# PCI.net
KiCad netlist of a schematic drawn in Altium Designer
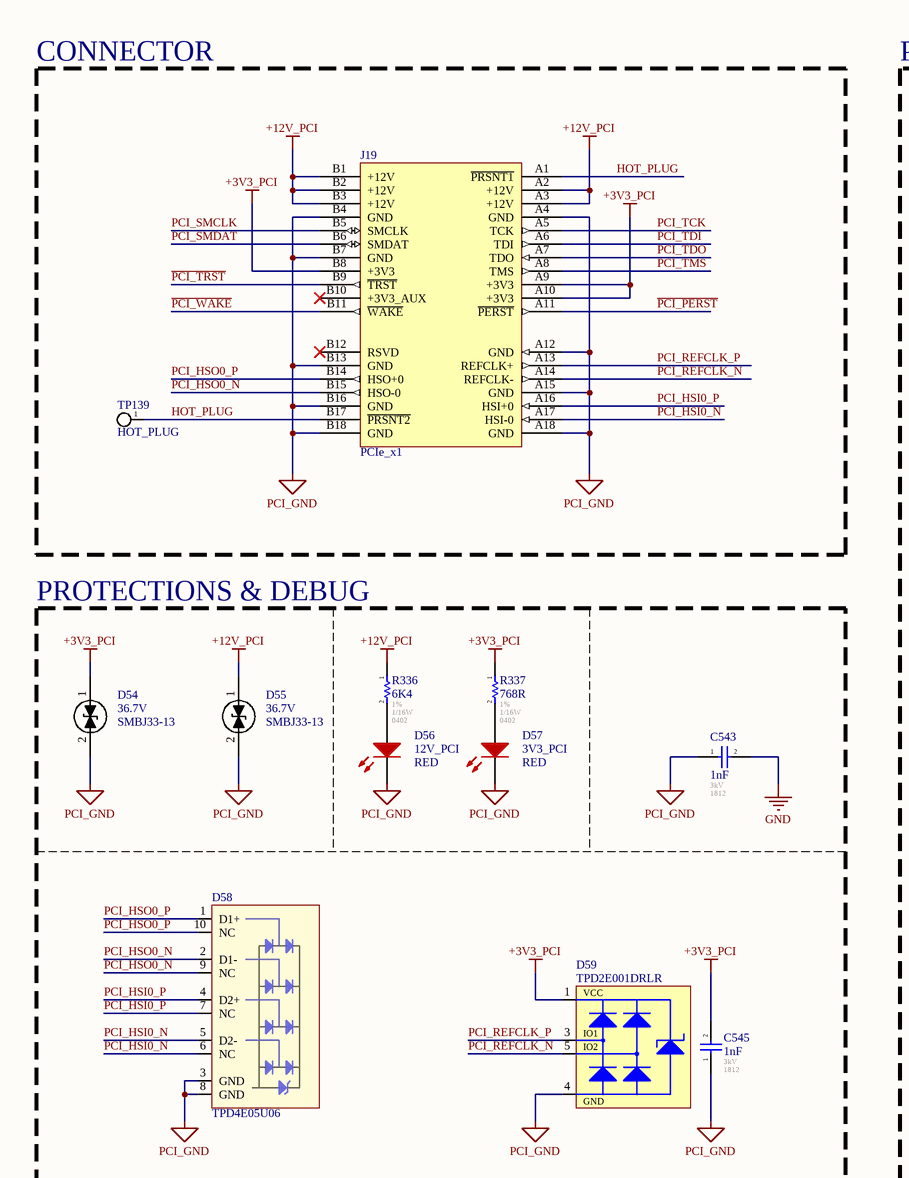
[diagram p0: PCI.SchDoc, top left]
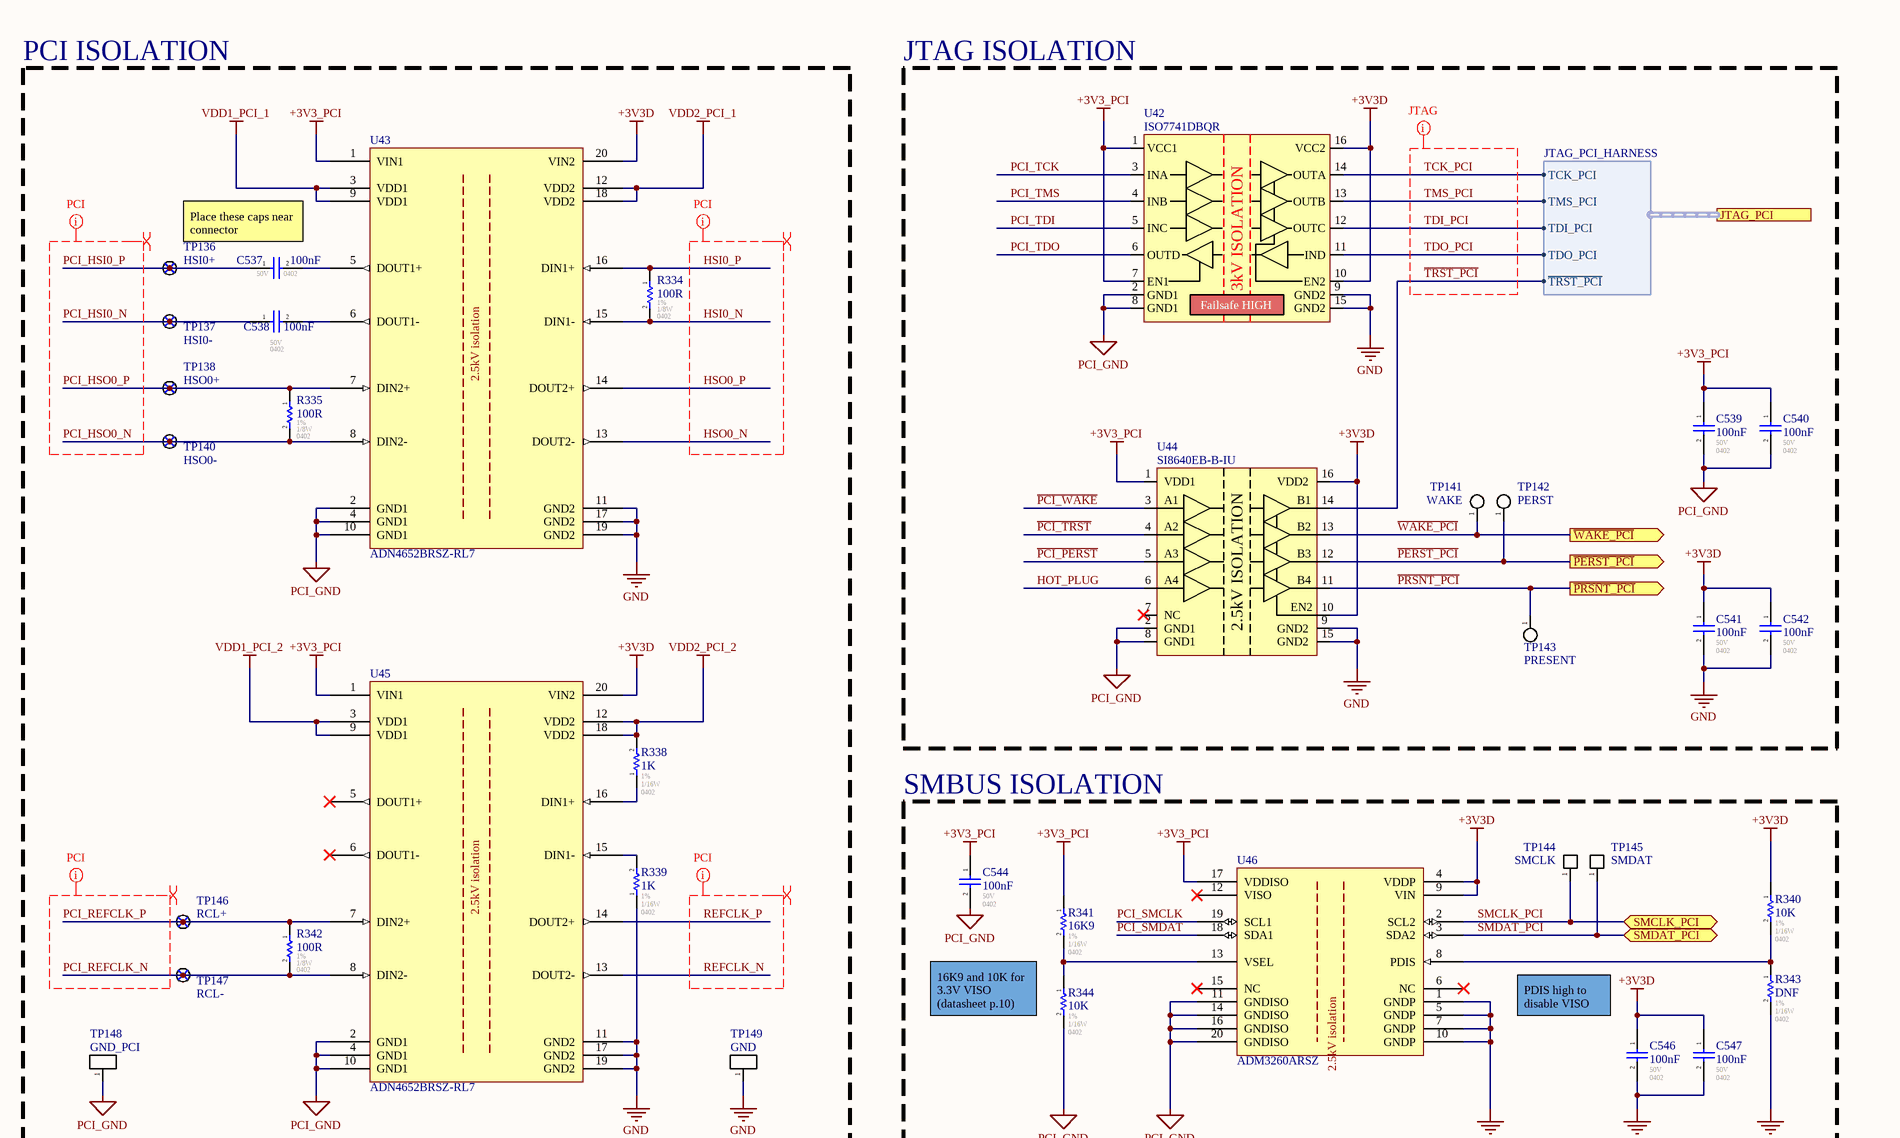
[diagram p1: PCI.SchDoc, top right]
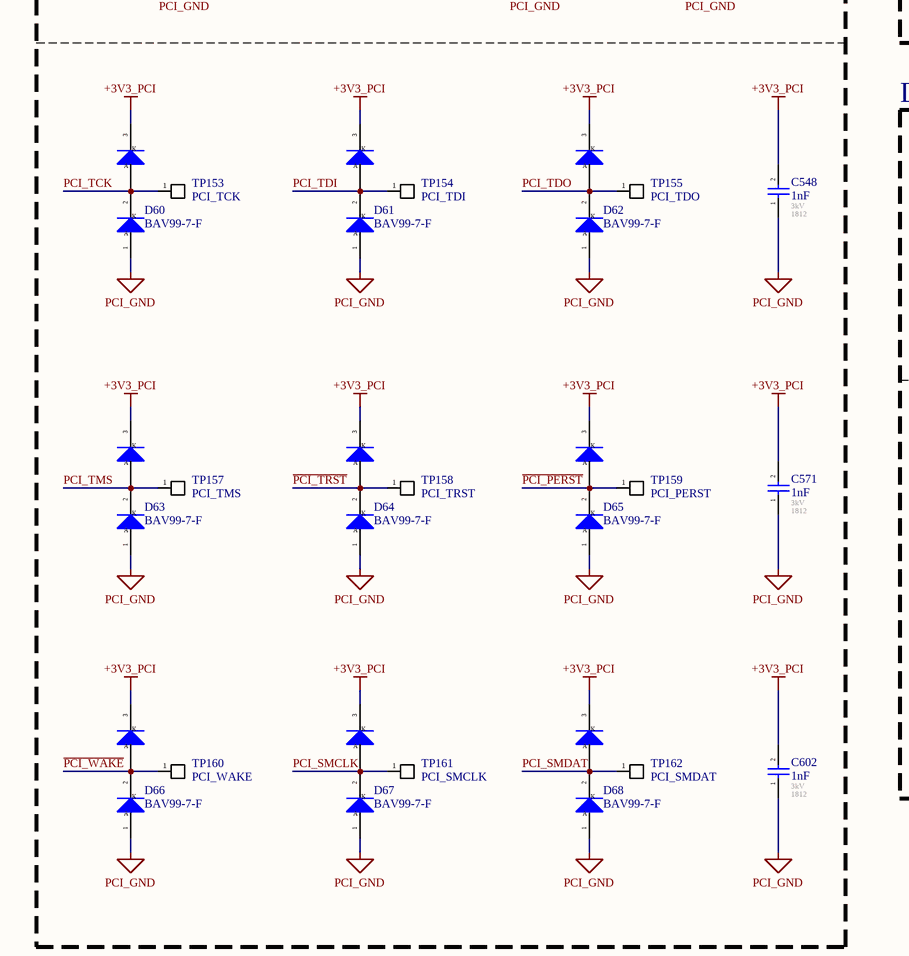
[diagram p2: PCI.SchDoc, bottom left]
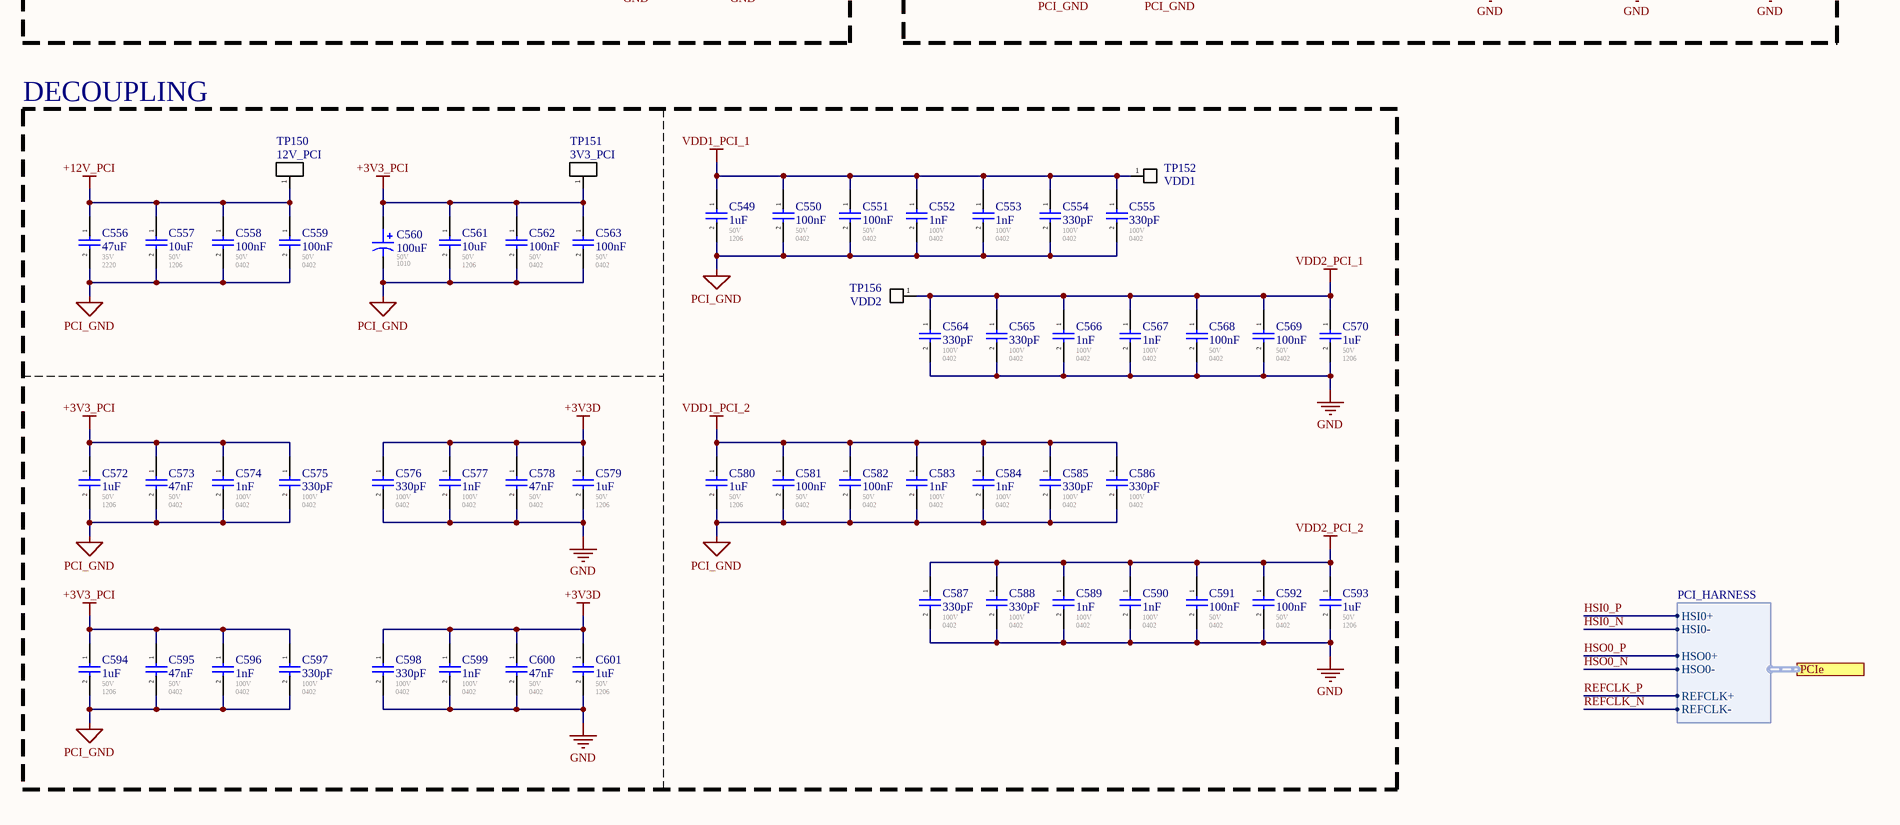
[diagram p3: PCI.SchDoc, bottom right]

(export (version "E")
  (design (tool "Eeschema 10.0.6"))
  (components
    (comp (ref "C537")
      (value "100nF")
      (footprint "0402")
      (description "GCM155R71H104KE02J\r\n0402 100nF 10% X7R Ceramic Capacitor")
      (fields
        (field (name "MFR") "Murata")
        (field (name "PART#") "GCM155R71H104KE02J")
        (field (name "VOLTAGE - RATED") "50V")
      )
      (libsource (lib "Symbols") (part "CAP_CER"))
    )
    (comp (ref "C538")
      (value "100nF")
      (footprint "0402")
      (description "GCM155R71H104KE02J\r\n0402 100nF 10% X7R Ceramic Capacitor")
      (fields
        (field (name "MFR") "Murata")
        (field (name "PART#") "GCM155R71H104KE02J")
        (field (name "VOLTAGE - RATED") "50V")
      )
      (libsource (lib "Symbols") (part "CAP_CER"))
    )
    (comp (ref "C539")
      (value "100nF")
      (footprint "0402")
      (description "GCM155R71H104KE02J\r\n0402 100nF 10% X7R Ceramic Capacitor")
      (fields
        (field (name "MFR") "Murata")
        (field (name "PART#") "GCM155R71H104KE02J")
        (field (name "VOLTAGE - RATED") "50V")
      )
      (libsource (lib "Symbols") (part "CAP_CER"))
    )
    (comp (ref "C540")
      (value "100nF")
      (footprint "0402")
      (description "GCM155R71H104KE02J\r\n0402 100nF 10% X7R Ceramic Capacitor")
      (fields
        (field (name "MFR") "Murata")
        (field (name "PART#") "GCM155R71H104KE02J")
        (field (name "VOLTAGE - RATED") "50V")
      )
      (libsource (lib "Symbols") (part "CAP_CER"))
    )
    (comp (ref "C541")
      (value "100nF")
      (footprint "0402")
      (description "GCM155R71H104KE02J\r\n0402 100nF 10% X7R Ceramic Capacitor")
      (fields
        (field (name "MFR") "Murata")
        (field (name "PART#") "GCM155R71H104KE02J")
        (field (name "VOLTAGE - RATED") "50V")
      )
      (libsource (lib "Symbols") (part "CAP_CER"))
    )
    (comp (ref "C542")
      (value "100nF")
      (footprint "0402")
      (description "GCM155R71H104KE02J\r\n0402 100nF 10% X7R Ceramic Capacitor")
      (fields
        (field (name "MFR") "Murata")
        (field (name "PART#") "GCM155R71H104KE02J")
        (field (name "VOLTAGE - RATED") "50V")
      )
      (libsource (lib "Symbols") (part "CAP_CER"))
    )
    (comp (ref "C543")
      (value "1nF")
      (footprint "1812")
      (description "C1812C102KHRACAUTO\r\n0402 470pF 10% X7R Ceramic Capacitor")
      (fields
        (field (name "MFR") "KEMET")
        (field (name "PART#") "C1812C102KHRACAUTO")
        (field (name "VOLTAGE - RATED") "3kV")
      )
      (libsource (lib "Symbols") (part "CAP_CER"))
    )
    (comp (ref "C544")
      (value "100nF")
      (footprint "0402")
      (description "GCM155R71H104KE02J\r\n0402 100nF 10% X7R Ceramic Capacitor")
      (fields
        (field (name "MFR") "Murata")
        (field (name "PART#") "GCM155R71H104KE02J")
        (field (name "VOLTAGE - RATED") "50V")
      )
      (libsource (lib "Symbols") (part "CAP_CER"))
    )
    (comp (ref "C545")
      (value "1nF")
      (footprint "1812")
      (description "C1812C102KHRACAUTO\r\n0402 470pF 10% X7R Ceramic Capacitor")
      (fields
        (field (name "MFR") "KEMET")
        (field (name "PART#") "C1812C102KHRACAUTO")
        (field (name "VOLTAGE - RATED") "3kV")
      )
      (libsource (lib "Symbols") (part "CAP_CER"))
    )
    (comp (ref "C546")
      (value "100nF")
      (footprint "0402")
      (description "GCM155R71H104KE02J\r\n0402 100nF 10% X7R Ceramic Capacitor")
      (fields
        (field (name "MFR") "Murata")
        (field (name "PART#") "GCM155R71H104KE02J")
        (field (name "VOLTAGE - RATED") "50V")
      )
      (libsource (lib "Symbols") (part "CAP_CER"))
    )
    (comp (ref "C547")
      (value "100nF")
      (footprint "0402")
      (description "GCM155R71H104KE02J\r\n0402 100nF 10% X7R Ceramic Capacitor")
      (fields
        (field (name "MFR") "Murata")
        (field (name "PART#") "GCM155R71H104KE02J")
        (field (name "VOLTAGE - RATED") "50V")
      )
      (libsource (lib "Symbols") (part "CAP_CER"))
    )
    (comp (ref "C548")
      (value "1nF")
      (footprint "1812")
      (description "C1812C102KHRACAUTO\r\n0402 470pF 10% X7R Ceramic Capacitor")
      (fields
        (field (name "MFR") "KEMET")
        (field (name "PART#") "C1812C102KHRACAUTO")
        (field (name "VOLTAGE - RATED") "3kV")
      )
      (libsource (lib "Symbols") (part "CAP_CER"))
    )
    (comp (ref "C549")
      (value "1uF")
      (footprint "1206")
      (description "GCJ31CR71H105KA12L\r\n1206 1uF 10% X7R Ceramic Capacitor")
      (fields
        (field (name "MFR") "Murata")
        (field (name "PART#") "GCJ31CR71H105KA12L")
        (field (name "VOLTAGE - RATED") "50V")
      )
      (libsource (lib "Symbols") (part "CAP_CER"))
    )
    (comp (ref "C550")
      (value "100nF")
      (footprint "0402")
      (description "GCM155R71H104KE02J\r\n0402 100nF 10% X7R Ceramic Capacitor")
      (fields
        (field (name "MFR") "Murata")
        (field (name "PART#") "GCM155R71H104KE02J")
        (field (name "VOLTAGE - RATED") "50V")
      )
      (libsource (lib "Symbols") (part "CAP_CER"))
    )
    (comp (ref "C551")
      (value "100nF")
      (footprint "0402")
      (description "GCM155R71H104KE02J\r\n0402 100nF 10% X7R Ceramic Capacitor")
      (fields
        (field (name "MFR") "Murata")
        (field (name "PART#") "GCM155R71H104KE02J")
        (field (name "VOLTAGE - RATED") "50V")
      )
      (libsource (lib "Symbols") (part "CAP_CER"))
    )
    (comp (ref "C552")
      (value "1nF")
      (footprint "0402")
      (description "GCM155R72A102KA37D\r\n0402 1nF 10% X7R Ceramic Capacitor")
      (fields
        (field (name "MFR") "Murata")
        (field (name "PART#") "GCM155R72A102KA37D")
        (field (name "VOLTAGE - RATED") "100V")
      )
      (libsource (lib "Symbols") (part "CAP_CER"))
    )
    (comp (ref "C553")
      (value "1nF")
      (footprint "0402")
      (description "GCM155R72A102KA37D\r\n0402 1nF 10% X7R Ceramic Capacitor")
      (fields
        (field (name "MFR") "Murata")
        (field (name "PART#") "GCM155R72A102KA37D")
        (field (name "VOLTAGE - RATED") "100V")
      )
      (libsource (lib "Symbols") (part "CAP_CER"))
    )
    (comp (ref "C554")
      (value "330pF")
      (footprint "0402")
      (description "GCM155R72A331KA37D\r\n0402 330pF 10% X7R Ceramic Capacitor")
      (fields
        (field (name "MFR") "Murata")
        (field (name "PART#") "GCM155R72A331KA37D")
        (field (name "VOLTAGE - RATED") "100V")
      )
      (libsource (lib "Symbols") (part "CAP_CER"))
    )
    (comp (ref "C555")
      (value "330pF")
      (footprint "0402")
      (description "GCM155R72A331KA37D\r\n0402 330pF 10% X7R Ceramic Capacitor")
      (fields
        (field (name "MFR") "Murata")
        (field (name "PART#") "GCM155R72A331KA37D")
        (field (name "VOLTAGE - RATED") "100V")
      )
      (libsource (lib "Symbols") (part "CAP_CER"))
    )
    (comp (ref "C556")
      (value "47uF")
      (footprint "2220")
      (description "CGA9N1X7R1V476M230KC\r\n2220 47uF 20% X7R Ceramic Capacitor")
      (fields
        (field (name "MFR") "TDK")
        (field (name "VOLTAGE - RATED") "35V")
        (field (name "TOLERANCE") "20%")
      )
      (libsource (lib "Symbols") (part "CAP_CER"))
    )
    (comp (ref "C557")
      (value "10uF")
      (footprint "1206")
      (description "GRT31CR61H106KE01L\r\n1206 10uF 10% X5R Ceramic Capacitor")
      (fields
        (field (name "MFR") "Murata")
        (field (name "VOLTAGE - RATED") "50V")
        (field (name "TOLERANCE") "10%")
      )
      (libsource (lib "Symbols") (part "CAP_CER"))
    )
    (comp (ref "C558")
      (value "100nF")
      (footprint "0402")
      (description "GCM155R71H104KE02J\r\n0402 100nF 10% X7R Ceramic Capacitor")
      (fields
        (field (name "MFR") "Murata")
        (field (name "PART#") "GCM155R71H104KE02J")
        (field (name "VOLTAGE - RATED") "50V")
      )
      (libsource (lib "Symbols") (part "CAP_CER"))
    )
    (comp (ref "C559")
      (value "100nF")
      (footprint "0402")
      (description "GCM155R71H104KE02J\r\n0402 100nF 10% X7R Ceramic Capacitor")
      (fields
        (field (name "MFR") "Murata")
        (field (name "PART#") "GCM155R71H104KE02J")
        (field (name "VOLTAGE - RATED") "50V")
      )
      (libsource (lib "Symbols") (part "CAP_CER"))
    )
    (comp (ref "C560")
      (value "100uF")
      (footprint "CAP_ALU_1010_vishay")
      (description "CAP - ALU 100uF 20% 50V - 1010")
      (fields
        (field (name "MFG") "Vishay Dale")
        (field (name "MFG PART NUMBER") "MAL215099101E3")
        (field (name "VOLTAGE") "50V")
        (field (name "PACKAGE") "1010")
        (field (name "CREATEDBY") "Jonathan Bouchard")
      )
      (libsource (lib "S7CAS_LIB2023") (part "CAP_ALU_MAL215099101E3"))
    )
    (comp (ref "C561")
      (value "10uF")
      (footprint "1206")
      (description "GRT31CR61H106KE01L\r\n1206 10uF 10% X5R Ceramic Capacitor")
      (fields
        (field (name "MFR") "Murata")
        (field (name "VOLTAGE - RATED") "50V")
        (field (name "TOLERANCE") "10%")
      )
      (libsource (lib "Symbols") (part "CAP_CER"))
    )
    (comp (ref "C562")
      (value "100nF")
      (footprint "0402")
      (description "GCM155R71H104KE02J\r\n0402 100nF 10% X7R Ceramic Capacitor")
      (fields
        (field (name "MFR") "Murata")
        (field (name "PART#") "GCM155R71H104KE02J")
        (field (name "VOLTAGE - RATED") "50V")
      )
      (libsource (lib "Symbols") (part "CAP_CER"))
    )
    (comp (ref "C563")
      (value "100nF")
      (footprint "0402")
      (description "GCM155R71H104KE02J\r\n0402 100nF 10% X7R Ceramic Capacitor")
      (fields
        (field (name "MFR") "Murata")
        (field (name "PART#") "GCM155R71H104KE02J")
        (field (name "VOLTAGE - RATED") "50V")
      )
      (libsource (lib "Symbols") (part "CAP_CER"))
    )
    (comp (ref "C564")
      (value "330pF")
      (footprint "0402")
      (description "GCM155R72A331KA37D\r\n0402 330pF 10% X7R Ceramic Capacitor")
      (fields
        (field (name "MFR") "Murata")
        (field (name "PART#") "GCM155R72A331KA37D")
        (field (name "VOLTAGE - RATED") "100V")
      )
      (libsource (lib "Symbols") (part "CAP_CER"))
    )
    (comp (ref "C565")
      (value "330pF")
      (footprint "0402")
      (description "GCM155R72A331KA37D\r\n0402 330pF 10% X7R Ceramic Capacitor")
      (fields
        (field (name "MFR") "Murata")
        (field (name "PART#") "GCM155R72A331KA37D")
        (field (name "VOLTAGE - RATED") "100V")
      )
      (libsource (lib "Symbols") (part "CAP_CER"))
    )
    (comp (ref "C566")
      (value "1nF")
      (footprint "0402")
      (description "GCM155R72A102KA37D\r\n0402 1nF 10% X7R Ceramic Capacitor")
      (fields
        (field (name "MFR") "Murata")
        (field (name "PART#") "GCM155R72A102KA37D")
        (field (name "VOLTAGE - RATED") "100V")
      )
      (libsource (lib "Symbols") (part "CAP_CER"))
    )
    (comp (ref "C567")
      (value "1nF")
      (footprint "0402")
      (description "GCM155R72A102KA37D\r\n0402 1nF 10% X7R Ceramic Capacitor")
      (fields
        (field (name "MFR") "Murata")
        (field (name "PART#") "GCM155R72A102KA37D")
        (field (name "VOLTAGE - RATED") "100V")
      )
      (libsource (lib "Symbols") (part "CAP_CER"))
    )
    (comp (ref "C568")
      (value "100nF")
      (footprint "0402")
      (description "GCM155R71H104KE02J\r\n0402 100nF 10% X7R Ceramic Capacitor")
      (fields
        (field (name "MFR") "Murata")
        (field (name "PART#") "GCM155R71H104KE02J")
        (field (name "VOLTAGE - RATED") "50V")
      )
      (libsource (lib "Symbols") (part "CAP_CER"))
    )
    (comp (ref "C569")
      (value "100nF")
      (footprint "0402")
      (description "GCM155R71H104KE02J\r\n0402 100nF 10% X7R Ceramic Capacitor")
      (fields
        (field (name "MFR") "Murata")
        (field (name "PART#") "GCM155R71H104KE02J")
        (field (name "VOLTAGE - RATED") "50V")
      )
      (libsource (lib "Symbols") (part "CAP_CER"))
    )
    (comp (ref "C570")
      (value "1uF")
      (footprint "1206")
      (description "GCJ31CR71H105KA12L\r\n1206 1uF 10% X7R Ceramic Capacitor")
      (fields
        (field (name "MFR") "Murata")
        (field (name "PART#") "GCJ31CR71H105KA12L")
        (field (name "VOLTAGE - RATED") "50V")
      )
      (libsource (lib "Symbols") (part "CAP_CER"))
    )
    (comp (ref "C571")
      (value "1nF")
      (footprint "1812")
      (description "C1812C102KHRACAUTO\r\n0402 470pF 10% X7R Ceramic Capacitor")
      (fields
        (field (name "MFR") "KEMET")
        (field (name "PART#") "C1812C102KHRACAUTO")
        (field (name "VOLTAGE - RATED") "3kV")
      )
      (libsource (lib "Symbols") (part "CAP_CER"))
    )
    (comp (ref "C572")
      (value "1uF")
      (footprint "1206")
      (description "GCJ31CR71H105KA12L\r\n1206 1uF 10% X7R Ceramic Capacitor")
      (fields
        (field (name "MFR") "Murata")
        (field (name "PART#") "GCJ31CR71H105KA12L")
        (field (name "VOLTAGE - RATED") "50V")
      )
      (libsource (lib "Symbols") (part "CAP_CER"))
    )
    (comp (ref "C573")
      (value "47nF")
      (footprint "0402")
      (description "GCM155R71H473KE02J\r\n0402 47nF 10% X7R Ceramic Capacitor")
      (fields
        (field (name "MFR") "Murata")
        (field (name "PART#") "GCM155R71H473KE02J")
        (field (name "VOLTAGE - RATED") "50V")
      )
      (libsource (lib "Symbols") (part "CAP_CER"))
    )
    (comp (ref "C574")
      (value "1nF")
      (footprint "0402")
      (description "GCM155R72A102KA37D\r\n0402 1nF 10% X7R Ceramic Capacitor")
      (fields
        (field (name "MFR") "Murata")
        (field (name "PART#") "GCM155R72A102KA37D")
        (field (name "VOLTAGE - RATED") "100V")
      )
      (libsource (lib "Symbols") (part "CAP_CER"))
    )
    (comp (ref "C575")
      (value "330pF")
      (footprint "0402")
      (description "GCM155R72A331KA37D\r\n0402 330pF 10% X7R Ceramic Capacitor")
      (fields
        (field (name "MFR") "Murata")
        (field (name "PART#") "GCM155R72A331KA37D")
        (field (name "VOLTAGE - RATED") "100V")
      )
      (libsource (lib "Symbols") (part "CAP_CER"))
    )
    (comp (ref "C576")
      (value "330pF")
      (footprint "0402")
      (description "GCM155R72A331KA37D\r\n0402 330pF 10% X7R Ceramic Capacitor")
      (fields
        (field (name "MFR") "Murata")
        (field (name "PART#") "GCM155R72A331KA37D")
        (field (name "VOLTAGE - RATED") "100V")
      )
      (libsource (lib "Symbols") (part "CAP_CER"))
    )
    (comp (ref "C577")
      (value "1nF")
      (footprint "0402")
      (description "GCM155R72A102KA37D\r\n0402 1nF 10% X7R Ceramic Capacitor")
      (fields
        (field (name "MFR") "Murata")
        (field (name "PART#") "GCM155R72A102KA37D")
        (field (name "VOLTAGE - RATED") "100V")
      )
      (libsource (lib "Symbols") (part "CAP_CER"))
    )
    (comp (ref "C578")
      (value "47nF")
      (footprint "0402")
      (description "GCM155R71H473KE02J\r\n0402 47nF 10% X7R Ceramic Capacitor")
      (fields
        (field (name "MFR") "Murata")
        (field (name "PART#") "GCM155R71H473KE02J")
        (field (name "VOLTAGE - RATED") "50V")
      )
      (libsource (lib "Symbols") (part "CAP_CER"))
    )
    (comp (ref "C579")
      (value "1uF")
      (footprint "1206")
      (description "GCJ31CR71H105KA12L\r\n1206 1uF 10% X7R Ceramic Capacitor")
      (fields
        (field (name "MFR") "Murata")
        (field (name "PART#") "GCJ31CR71H105KA12L")
        (field (name "VOLTAGE - RATED") "50V")
      )
      (libsource (lib "Symbols") (part "CAP_CER"))
    )
    (comp (ref "C580")
      (value "1uF")
      (footprint "1206")
      (description "GCJ31CR71H105KA12L\r\n1206 1uF 10% X7R Ceramic Capacitor")
      (fields
        (field (name "MFR") "Murata")
        (field (name "PART#") "GCJ31CR71H105KA12L")
        (field (name "VOLTAGE - RATED") "50V")
      )
      (libsource (lib "Symbols") (part "CAP_CER"))
    )
    (comp (ref "C581")
      (value "100nF")
      (footprint "0402")
      (description "GCM155R71H104KE02J\r\n0402 100nF 10% X7R Ceramic Capacitor")
      (fields
        (field (name "MFR") "Murata")
        (field (name "PART#") "GCM155R71H104KE02J")
        (field (name "VOLTAGE - RATED") "50V")
      )
      (libsource (lib "Symbols") (part "CAP_CER"))
    )
    (comp (ref "C582")
      (value "100nF")
      (footprint "0402")
      (description "GCM155R71H104KE02J\r\n0402 100nF 10% X7R Ceramic Capacitor")
      (fields
        (field (name "MFR") "Murata")
        (field (name "PART#") "GCM155R71H104KE02J")
        (field (name "VOLTAGE - RATED") "50V")
      )
      (libsource (lib "Symbols") (part "CAP_CER"))
    )
    (comp (ref "C583")
      (value "1nF")
      (footprint "0402")
      (description "GCM155R72A102KA37D\r\n0402 1nF 10% X7R Ceramic Capacitor")
      (fields
        (field (name "MFR") "Murata")
        (field (name "PART#") "GCM155R72A102KA37D")
        (field (name "VOLTAGE - RATED") "100V")
      )
      (libsource (lib "Symbols") (part "CAP_CER"))
    )
    (comp (ref "C584")
      (value "1nF")
      (footprint "0402")
      (description "GCM155R72A102KA37D\r\n0402 1nF 10% X7R Ceramic Capacitor")
      (fields
        (field (name "MFR") "Murata")
        (field (name "PART#") "GCM155R72A102KA37D")
        (field (name "VOLTAGE - RATED") "100V")
      )
      (libsource (lib "Symbols") (part "CAP_CER"))
    )
    (comp (ref "C585")
      (value "330pF")
      (footprint "0402")
      (description "GCM155R72A331KA37D\r\n0402 330pF 10% X7R Ceramic Capacitor")
      (fields
        (field (name "MFR") "Murata")
        (field (name "PART#") "GCM155R72A331KA37D")
        (field (name "VOLTAGE - RATED") "100V")
      )
      (libsource (lib "Symbols") (part "CAP_CER"))
    )
    (comp (ref "C586")
      (value "330pF")
      (footprint "0402")
      (description "GCM155R72A331KA37D\r\n0402 330pF 10% X7R Ceramic Capacitor")
      (fields
        (field (name "MFR") "Murata")
        (field (name "PART#") "GCM155R72A331KA37D")
        (field (name "VOLTAGE - RATED") "100V")
      )
      (libsource (lib "Symbols") (part "CAP_CER"))
    )
    (comp (ref "C587")
      (value "330pF")
      (footprint "0402")
      (description "GCM155R72A331KA37D\r\n0402 330pF 10% X7R Ceramic Capacitor")
      (fields
        (field (name "MFR") "Murata")
        (field (name "PART#") "GCM155R72A331KA37D")
        (field (name "VOLTAGE - RATED") "100V")
      )
      (libsource (lib "Symbols") (part "CAP_CER"))
    )
    (comp (ref "C588")
      (value "330pF")
      (footprint "0402")
      (description "GCM155R72A331KA37D\r\n0402 330pF 10% X7R Ceramic Capacitor")
      (fields
        (field (name "MFR") "Murata")
        (field (name "PART#") "GCM155R72A331KA37D")
        (field (name "VOLTAGE - RATED") "100V")
      )
      (libsource (lib "Symbols") (part "CAP_CER"))
    )
    (comp (ref "C589")
      (value "1nF")
      (footprint "0402")
      (description "GCM155R72A102KA37D\r\n0402 1nF 10% X7R Ceramic Capacitor")
      (fields
        (field (name "MFR") "Murata")
        (field (name "PART#") "GCM155R72A102KA37D")
        (field (name "VOLTAGE - RATED") "100V")
      )
      (libsource (lib "Symbols") (part "CAP_CER"))
    )
    (comp (ref "C590")
      (value "1nF")
      (footprint "0402")
      (description "GCM155R72A102KA37D\r\n0402 1nF 10% X7R Ceramic Capacitor")
      (fields
        (field (name "MFR") "Murata")
        (field (name "PART#") "GCM155R72A102KA37D")
        (field (name "VOLTAGE - RATED") "100V")
      )
      (libsource (lib "Symbols") (part "CAP_CER"))
    )
    (comp (ref "C591")
      (value "100nF")
      (footprint "0402")
      (description "GCM155R71H104KE02J\r\n0402 100nF 10% X7R Ceramic Capacitor")
      (fields
        (field (name "MFR") "Murata")
        (field (name "PART#") "GCM155R71H104KE02J")
        (field (name "VOLTAGE - RATED") "50V")
      )
      (libsource (lib "Symbols") (part "CAP_CER"))
    )
    (comp (ref "C592")
      (value "100nF")
      (footprint "0402")
      (description "GCM155R71H104KE02J\r\n0402 100nF 10% X7R Ceramic Capacitor")
      (fields
        (field (name "MFR") "Murata")
        (field (name "PART#") "GCM155R71H104KE02J")
        (field (name "VOLTAGE - RATED") "50V")
      )
      (libsource (lib "Symbols") (part "CAP_CER"))
    )
    (comp (ref "C593")
      (value "1uF")
      (footprint "1206")
      (description "GCJ31CR71H105KA12L\r\n1206 1uF 10% X7R Ceramic Capacitor")
      (fields
        (field (name "MFR") "Murata")
        (field (name "PART#") "GCJ31CR71H105KA12L")
        (field (name "VOLTAGE - RATED") "50V")
      )
      (libsource (lib "Symbols") (part "CAP_CER"))
    )
    (comp (ref "C594")
      (value "1uF")
      (footprint "1206")
      (description "GCJ31CR71H105KA12L\r\n1206 1uF 10% X7R Ceramic Capacitor")
      (fields
        (field (name "MFR") "Murata")
        (field (name "PART#") "GCJ31CR71H105KA12L")
        (field (name "VOLTAGE - RATED") "50V")
      )
      (libsource (lib "Symbols") (part "CAP_CER"))
    )
    (comp (ref "C595")
      (value "47nF")
      (footprint "0402")
      (description "GCM155R71H473KE02J\r\n0402 47nF 10% X7R Ceramic Capacitor")
      (fields
        (field (name "MFR") "Murata")
        (field (name "PART#") "GCM155R71H473KE02J")
        (field (name "VOLTAGE - RATED") "50V")
      )
      (libsource (lib "Symbols") (part "CAP_CER"))
    )
    (comp (ref "C596")
      (value "1nF")
      (footprint "0402")
      (description "GCM155R72A102KA37D\r\n0402 1nF 10% X7R Ceramic Capacitor")
      (fields
        (field (name "MFR") "Murata")
        (field (name "PART#") "GCM155R72A102KA37D")
        (field (name "VOLTAGE - RATED") "100V")
      )
      (libsource (lib "Symbols") (part "CAP_CER"))
    )
    (comp (ref "C597")
      (value "330pF")
      (footprint "0402")
      (description "GCM155R72A331KA37D\r\n0402 330pF 10% X7R Ceramic Capacitor")
      (fields
        (field (name "MFR") "Murata")
        (field (name "PART#") "GCM155R72A331KA37D")
        (field (name "VOLTAGE - RATED") "100V")
      )
      (libsource (lib "Symbols") (part "CAP_CER"))
    )
    (comp (ref "C598")
      (value "330pF")
      (footprint "0402")
      (description "GCM155R72A331KA37D\r\n0402 330pF 10% X7R Ceramic Capacitor")
      (fields
        (field (name "MFR") "Murata")
        (field (name "PART#") "GCM155R72A331KA37D")
        (field (name "VOLTAGE - RATED") "100V")
      )
      (libsource (lib "Symbols") (part "CAP_CER"))
    )
    (comp (ref "C599")
      (value "1nF")
      (footprint "0402")
      (description "GCM155R72A102KA37D\r\n0402 1nF 10% X7R Ceramic Capacitor")
      (fields
        (field (name "MFR") "Murata")
        (field (name "PART#") "GCM155R72A102KA37D")
        (field (name "VOLTAGE - RATED") "100V")
      )
      (libsource (lib "Symbols") (part "CAP_CER"))
    )
    (comp (ref "C600")
      (value "47nF")
      (footprint "0402")
      (description "GCM155R71H473KE02J\r\n0402 47nF 10% X7R Ceramic Capacitor")
      (fields
        (field (name "MFR") "Murata")
        (field (name "PART#") "GCM155R71H473KE02J")
        (field (name "VOLTAGE - RATED") "50V")
      )
      (libsource (lib "Symbols") (part "CAP_CER"))
    )
    (comp (ref "C601")
      (value "1uF")
      (footprint "1206")
      (description "GCJ31CR71H105KA12L\r\n1206 1uF 10% X7R Ceramic Capacitor")
      (fields
        (field (name "MFR") "Murata")
        (field (name "PART#") "GCJ31CR71H105KA12L")
        (field (name "VOLTAGE - RATED") "50V")
      )
      (libsource (lib "Symbols") (part "CAP_CER"))
    )
    (comp (ref "C602")
      (value "1nF")
      (footprint "1812")
      (description "C1812C102KHRACAUTO\r\n0402 470pF 10% X7R Ceramic Capacitor")
      (fields
        (field (name "MFR") "KEMET")
        (field (name "PART#") "C1812C102KHRACAUTO")
        (field (name "VOLTAGE - RATED") "3kV")
      )
      (libsource (lib "Symbols") (part "CAP_CER"))
    )
    (comp (ref "D54")
      (value "SMBJ33-13")
      (footprint "DO214AA (SMB)")
      (description "53.3V Clamp 11.3A Ipp Tvs Diode Surface Mount SMB")
      (fields (field (name "MFR") "SMBJ33CAQ-13-F") (field (name "VOLTAGE - BREAKDOWN") "36.7V"))
      (libsource (lib "Symbols") (part "DIODE_TVS"))
    )
    (comp (ref "D55")
      (value "SMBJ33-13")
      (footprint "DO214AA (SMB)")
      (description "53.3V Clamp 11.3A Ipp Tvs Diode Surface Mount SMB")
      (fields (field (name "MFR") "SMBJ33CAQ-13-F") (field (name "VOLTAGE - BREAKDOWN") "36.7V"))
      (libsource (lib "Symbols") (part "DIODE_TVS"))
    )
    (comp (ref "D56")
      (value "12V_PCI")
      (footprint "LED_0603")
      (description "LED - 620nM RED 2mA - 0603")
      (fields
        (field (name "VOLTAGE") "1.8V")
        (field (name "MFG") "ROHM Semiconductor")
        (field (name "ALTIUM_VALUE") "RED")
        (field (name "CREATEDBY") "Jonathan Bouchard")
      )
      (libsource (lib "S7CAS_LIB2023") (part "LED_SML-311UTT86"))
    )
    (comp (ref "D57")
      (value "3V3_PCI")
      (footprint "LED_0603")
      (description "LED - 620nM RED 2mA - 0603")
      (fields
        (field (name "VOLTAGE") "1.8V")
        (field (name "MFG") "ROHM Semiconductor")
        (field (name "ALTIUM_VALUE") "RED")
        (field (name "CREATEDBY") "Jonathan Bouchard")
      )
      (libsource (lib "S7CAS_LIB2023") (part "LED_SML-311UTT86"))
    )
    (comp (ref "D58")
      (value "TPD4E05U06")
      (footprint "TVS_DATA_TPD4E05U06")
      (description "TVS - TVS DIODE 5.5VWM 14VC - 10SON")
      (fields
        (field (name "CREATEDBY/DATE") "Olivier Bernard / 12/3/2018")
        (field (name "VERIFIEDBY") "Caroline Paulin / 4 juillet 2018")
      )
      (libsource (lib "S7CAS_LIB2023") (part "TVS_DATA_TPD4E05U06"))
    )
    (comp (ref "D59")
      (value "TPD2E001DRLR")
      (footprint "TVS_USB_TPD2E001DRLR")
      (description "TVS - USB TVS DIODE 5.5V - SOT-553")
      (fields
        (field (name "CREATEDBY/DATE") "Jonathan Bouchard 2018-07-10")
        (field (name "VERIFIEDBY") "Arnaud Samson 16-07-18")
      )
      (libsource (lib "S7CAS_LIB2023") (part "TVS_USB_TPD2E001DRLR"))
    )
    (comp (ref "D60")
      (value "BAV99-7-F")
      (footprint "SOT23-3")
      (description "Diode Array 1 Pair Series Connection 75 V 300mA (DC) Surface Mount TO-236-3, SC-59, SOT-23-3")
      (fields (field (name "MFR") "Diodes Incorporated"))
      (libsource (lib "Symbols") (part "DIODE_TVS_DUAL"))
    )
    (comp (ref "D61")
      (value "BAV99-7-F")
      (footprint "SOT23-3")
      (description "Diode Array 1 Pair Series Connection 75 V 300mA (DC) Surface Mount TO-236-3, SC-59, SOT-23-3")
      (fields (field (name "MFR") "Diodes Incorporated"))
      (libsource (lib "Symbols") (part "DIODE_TVS_DUAL"))
    )
    (comp (ref "D62")
      (value "BAV99-7-F")
      (footprint "SOT23-3")
      (description "Diode Array 1 Pair Series Connection 75 V 300mA (DC) Surface Mount TO-236-3, SC-59, SOT-23-3")
      (fields (field (name "MFR") "Diodes Incorporated"))
      (libsource (lib "Symbols") (part "DIODE_TVS_DUAL"))
    )
    (comp (ref "D63")
      (value "BAV99-7-F")
      (footprint "SOT23-3")
      (description "Diode Array 1 Pair Series Connection 75 V 300mA (DC) Surface Mount TO-236-3, SC-59, SOT-23-3")
      (fields (field (name "MFR") "Diodes Incorporated"))
      (libsource (lib "Symbols") (part "DIODE_TVS_DUAL"))
    )
    (comp (ref "D64")
      (value "BAV99-7-F")
      (footprint "SOT23-3")
      (description "Diode Array 1 Pair Series Connection 75 V 300mA (DC) Surface Mount TO-236-3, SC-59, SOT-23-3")
      (fields (field (name "MFR") "Diodes Incorporated"))
      (libsource (lib "Symbols") (part "DIODE_TVS_DUAL"))
    )
    (comp (ref "D65")
      (value "BAV99-7-F")
      (footprint "SOT23-3")
      (description "Diode Array 1 Pair Series Connection 75 V 300mA (DC) Surface Mount TO-236-3, SC-59, SOT-23-3")
      (fields (field (name "MFR") "Diodes Incorporated"))
      (libsource (lib "Symbols") (part "DIODE_TVS_DUAL"))
    )
    (comp (ref "D66")
      (value "BAV99-7-F")
      (footprint "SOT23-3")
      (description "Diode Array 1 Pair Series Connection 75 V 300mA (DC) Surface Mount TO-236-3, SC-59, SOT-23-3")
      (fields (field (name "MFR") "Diodes Incorporated"))
      (libsource (lib "Symbols") (part "DIODE_TVS_DUAL"))
    )
    (comp (ref "D67")
      (value "BAV99-7-F")
      (footprint "SOT23-3")
      (description "Diode Array 1 Pair Series Connection 75 V 300mA (DC) Surface Mount TO-236-3, SC-59, SOT-23-3")
      (fields (field (name "MFR") "Diodes Incorporated"))
      (libsource (lib "Symbols") (part "DIODE_TVS_DUAL"))
    )
    (comp (ref "D68")
      (value "BAV99-7-F")
      (footprint "SOT23-3")
      (description "Diode Array 1 Pair Series Connection 75 V 300mA (DC) Surface Mount TO-236-3, SC-59, SOT-23-3")
      (fields (field (name "MFR") "Diodes Incorporated"))
      (libsource (lib "Symbols") (part "DIODE_TVS_DUAL"))
    )
    (comp (ref "J19") (value "PCIe_x1") (footprint "PCIe_x1") (libsource (lib "Connectors") (part "PCIe_x1")))
    (comp (ref "R334")
      (value "100R")
      (footprint "RES_0402")
      (fields
        (field (name "TOLERANCE") "1%")
        (field (name "POWER") "1/8W")
        (field (name "PACKAGE / CASE") "0402")
      )
      (libsource (lib "Symbols") (part "RESISTOR"))
    )
    (comp (ref "R335")
      (value "100R")
      (footprint "RES_0402")
      (fields
        (field (name "TOLERANCE") "1%")
        (field (name "POWER") "1/8W")
        (field (name "PACKAGE / CASE") "0402")
      )
      (libsource (lib "Symbols") (part "RESISTOR"))
    )
    (comp (ref "R336")
      (value "6K4")
      (footprint "RES_0402")
      (fields
        (field (name "TOLERANCE") "1%")
        (field (name "POWER") "1/16W")
        (field (name "PACKAGE / CASE") "0402")
      )
      (libsource (lib "Symbols") (part "RESISTOR"))
    )
    (comp (ref "R337")
      (value "768R")
      (footprint "RES_0402")
      (fields
        (field (name "TOLERANCE") "1%")
        (field (name "POWER") "1/16W")
        (field (name "PACKAGE / CASE") "0402")
      )
      (libsource (lib "Symbols") (part "RESISTOR"))
    )
    (comp (ref "R338")
      (value "1K")
      (footprint "RES_0402")
      (fields
        (field (name "TOLERANCE") "1%")
        (field (name "POWER") "1/16W")
        (field (name "PACKAGE / CASE") "0402")
      )
      (libsource (lib "Symbols") (part "RESISTOR"))
    )
    (comp (ref "R339")
      (value "1K")
      (footprint "RES_0402")
      (fields
        (field (name "TOLERANCE") "1%")
        (field (name "POWER") "1/16W")
        (field (name "PACKAGE / CASE") "0402")
      )
      (libsource (lib "Symbols") (part "RESISTOR"))
    )
    (comp (ref "R340")
      (value "10K")
      (footprint "RES_0402")
      (fields
        (field (name "TOLERANCE") "1%")
        (field (name "POWER") "1/16W")
        (field (name "PACKAGE / CASE") "0402")
      )
      (libsource (lib "Symbols") (part "RESISTOR"))
    )
    (comp (ref "R341")
      (value "16K9")
      (footprint "RES_0402")
      (fields
        (field (name "TOLERANCE") "1%")
        (field (name "POWER") "1/16W")
        (field (name "PACKAGE / CASE") "0402")
      )
      (libsource (lib "Symbols") (part "RESISTOR"))
    )
    (comp (ref "R342")
      (value "100R")
      (footprint "RES_0402")
      (fields
        (field (name "TOLERANCE") "1%")
        (field (name "POWER") "1/8W")
        (field (name "PACKAGE / CASE") "0402")
      )
      (libsource (lib "Symbols") (part "RESISTOR"))
    )
    (comp (ref "R343")
      (value "DNF")
      (footprint "RES_0402")
      (fields
        (field (name "TOLERANCE") "1%")
        (field (name "POWER") "1/16W")
        (field (name "PACKAGE / CASE") "0402")
      )
      (libsource (lib "Symbols") (part "RESISTOR"))
    )
    (comp (ref "R344")
      (value "10K")
      (footprint "RES_0402")
      (fields
        (field (name "TOLERANCE") "1%")
        (field (name "POWER") "1/16W")
        (field (name "PACKAGE / CASE") "0402")
      )
      (libsource (lib "Symbols") (part "RESISTOR"))
    )
    (comp (ref "TP136")
      (value "HSI0+")
      (footprint "TP_PAD_TINY")
      (description "Test Point")
      (libsource (lib "Symbols") (part "TESTPOINT_PAD_TINY"))
    )
    (comp (ref "TP137")
      (value "HSI0-")
      (footprint "TP_PAD_TINY")
      (description "Test Point")
      (libsource (lib "Symbols") (part "TESTPOINT_PAD_TINY"))
    )
    (comp (ref "TP138")
      (value "HSO0+")
      (footprint "TP_PAD_TINY")
      (description "Test Point")
      (libsource (lib "Symbols") (part "TESTPOINT_PAD_TINY"))
    )
    (comp (ref "TP139")
      (value "HOT_PLUG")
      (footprint "TP_PAD_SMALL")
      (description "Test Point")
      (libsource (lib "Symbols") (part "TESTPOINT_PAD_SMALL"))
    )
    (comp (ref "TP140")
      (value "HSO0-")
      (footprint "TP_PAD_TINY")
      (description "Test Point")
      (libsource (lib "Symbols") (part "TESTPOINT_PAD_TINY"))
    )
    (comp (ref "TP141")
      (value "WAKE")
      (footprint "TP_PAD_SMALL")
      (description "Test Point")
      (libsource (lib "Symbols") (part "TESTPOINT_PAD_SMALL"))
    )
    (comp (ref "TP142")
      (value "PERST")
      (footprint "TP_PAD_SMALL")
      (description "Test Point")
      (libsource (lib "Symbols") (part "TESTPOINT_PAD_SMALL"))
    )
    (comp (ref "TP143")
      (value "PRESENT")
      (footprint "TP_PAD_SMALL")
      (description "Test Point")
      (libsource (lib "Symbols") (part "TESTPOINT_PAD_SMALL"))
    )
    (comp (ref "TP144")
      (value "SMCLK")
      (footprint "TP_PAD")
      (description "Test Point")
      (libsource (lib "Symbols") (part "TESTPOINT_PAD"))
    )
    (comp (ref "TP145")
      (value "SMDAT")
      (footprint "TP_PAD")
      (description "Test Point")
      (libsource (lib "Symbols") (part "TESTPOINT_PAD"))
    )
    (comp (ref "TP146")
      (value "RCL+")
      (footprint "TP_PAD_TINY")
      (description "Test Point")
      (libsource (lib "Symbols") (part "TESTPOINT_PAD_TINY"))
    )
    (comp (ref "TP147")
      (value "RCL-")
      (footprint "TP_PAD_TINY")
      (description "Test Point")
      (libsource (lib "Symbols") (part "TESTPOINT_PAD_TINY"))
    )
    (comp (ref "TP148")
      (value "GND_PCI")
      (footprint "TP_HOLE")
      (description "Test Point")
      (libsource (lib "Symbols") (part "TESTPOINT"))
    )
    (comp (ref "TP149")
      (value "GND")
      (footprint "TP_HOLE")
      (description "Test Point")
      (libsource (lib "Symbols") (part "TESTPOINT"))
    )
    (comp (ref "TP150")
      (value "12V_PCI")
      (footprint "TP_HOLE")
      (description "Test Point")
      (libsource (lib "Symbols") (part "TESTPOINT"))
    )
    (comp (ref "TP151")
      (value "3V3_PCI")
      (footprint "TP_HOLE")
      (description "Test Point")
      (libsource (lib "Symbols") (part "TESTPOINT"))
    )
    (comp (ref "TP152")
      (value "VDD1")
      (footprint "TP_PAD")
      (description "Test Point")
      (libsource (lib "Symbols") (part "TESTPOINT_PAD"))
    )
    (comp (ref "TP153")
      (value "PCI_TCK")
      (footprint "TP_PAD")
      (description "Test Point")
      (libsource (lib "Symbols") (part "TESTPOINT_PAD"))
    )
    (comp (ref "TP154")
      (value "PCI_TDI")
      (footprint "TP_PAD")
      (description "Test Point")
      (libsource (lib "Symbols") (part "TESTPOINT_PAD"))
    )
    (comp (ref "TP155")
      (value "PCI_TDO")
      (footprint "TP_PAD")
      (description "Test Point")
      (libsource (lib "Symbols") (part "TESTPOINT_PAD"))
    )
    (comp (ref "TP156")
      (value "VDD2")
      (footprint "TP_PAD")
      (description "Test Point")
      (libsource (lib "Symbols") (part "TESTPOINT_PAD"))
    )
    (comp (ref "TP157")
      (value "PCI_TMS")
      (footprint "TP_PAD")
      (description "Test Point")
      (libsource (lib "Symbols") (part "TESTPOINT_PAD"))
    )
    (comp (ref "TP158")
      (value "PCI_TRST")
      (footprint "TP_PAD")
      (description "Test Point")
      (libsource (lib "Symbols") (part "TESTPOINT_PAD"))
    )
    (comp (ref "TP159")
      (value "PCI_PERST")
      (footprint "TP_PAD")
      (description "Test Point")
      (libsource (lib "Symbols") (part "TESTPOINT_PAD"))
    )
    (comp (ref "TP160")
      (value "PCI_WAKE")
      (footprint "TP_PAD")
      (description "Test Point")
      (libsource (lib "Symbols") (part "TESTPOINT_PAD"))
    )
    (comp (ref "TP161")
      (value "PCI_SMCLK")
      (footprint "TP_PAD")
      (description "Test Point")
      (libsource (lib "Symbols") (part "TESTPOINT_PAD"))
    )
    (comp (ref "TP162")
      (value "PCI_SMDAT")
      (footprint "TP_PAD")
      (description "Test Point")
      (libsource (lib "Symbols") (part "TESTPOINT_PAD"))
    )
    (comp (ref "U42")
      (value "ISO7741DBQR")
      (footprint "ISO_ISO7741DBQR")
      (description "ISO - Quad-Channel Digital Isolator 3/1 (Default High)- 16-SSOP")
      (fields
        (field (name "CREATEDBY/DATE") "Louis-Daniel Gaulin / 11-03-2020")
        (field (name "VERIFIEDBY") "C.Paulin - 20/04/2020")
      )
      (libsource (lib "S7CAS_LIB2023") (part "ISO_ISO7741DBQR"))
    )
    (comp (ref "U43")
      (value "ADN4652BRSZ-RL7")
      (footprint "TSSOP-20_5.3MM")
      (fields (field (name "MFR") "Analog Devices"))
      (libsource (lib "Misc") (part "ADN4652BRSZ-RL7"))
    )
    (comp (ref "U44")
      (value "SI8640EB-B-IU")
      (footprint "ISO_SI8640EB-B-IU")
      (description "ISO - Quad-Channel Digital Isolator (default HI) - 16-SSOP")
      (fields
        (field (name "CREATEDBY/DATE") "Joel Lemay 2018-06-05")
        (field (name "VERIFIEDBY") "Caroline Paulin - 12 sept 2018")
      )
      (libsource (lib "S7CAS_LIB2023") (part "ISO_SI8640EB-B-IU"))
    )
    (comp (ref "U45")
      (value "ADN4652BRSZ-RL7")
      (footprint "TSSOP-20_5.3MM")
      (fields (field (name "MFR") "Analog Devices"))
      (libsource (lib "Misc") (part "ADN4652BRSZ-RL7"))
    )
    (comp (ref "U46")
      (value "ADM3260ARSZ")
      (footprint "TSSOP-20_5.3MM")
      (description "I2C Digital Isolator 2500Vrms 2 Channel 25kV/µs CMTI 20-SSOP (0.209\", 5.30mm Width)")
      (fields (field (name "MFR") "Analog Devices"))
      (libsource (lib "Misc") (part "ADM3260ARSZ"))
    )
  )
  (nets
    (net (code "3") (name "+3V3D") (class "Default")
      (node (ref "C541") (pin "1") (pinfunction "1_1") (pintype "passive"))
      (node (ref "C542") (pin "1") (pinfunction "1_1") (pintype "passive"))
      (node (ref "C546") (pin "1") (pinfunction "1_1") (pintype "passive"))
      (node (ref "C547") (pin "1") (pinfunction "1_1") (pintype "passive"))
      (node (ref "C576") (pin "1") (pinfunction "1_1") (pintype "passive"))
      (node (ref "C577") (pin "1") (pinfunction "1_1") (pintype "passive"))
      (node (ref "C578") (pin "1") (pinfunction "1_1") (pintype "passive"))
      (node (ref "C579") (pin "1") (pinfunction "1_1") (pintype "passive"))
      (node (ref "C598") (pin "1") (pinfunction "1_1") (pintype "passive"))
      (node (ref "C599") (pin "1") (pinfunction "1_1") (pintype "passive"))
      (node (ref "C600") (pin "1") (pinfunction "1_1") (pintype "passive"))
      (node (ref "C601") (pin "1") (pinfunction "1_1") (pintype "passive"))
      (node (ref "R340") (pin "1") (pinfunction "1_1") (pintype "passive"))
      (node (ref "U42") (pin "10") (pinfunction "EN2_10") (pintype "passive"))
      (node (ref "U42") (pin "16") (pinfunction "VCC2_16") (pintype "passive"))
      (node (ref "U43") (pin "20") (pinfunction "VIN2_20") (pintype "power_in"))
      (node (ref "U44") (pin "10") (pinfunction "EN2_10") (pintype "passive"))
      (node (ref "U44") (pin "16") (pinfunction "VDD2_16") (pintype "passive"))
      (node (ref "U45") (pin "20") (pinfunction "VIN2_20") (pintype "power_in"))
      (node (ref "U46") (pin "4") (pinfunction "VDDP_4") (pintype "power_in"))
      (node (ref "U46") (pin "9") (pinfunction "VIN_9") (pintype "power_in"))
    )
    (net (code "4") (name "+3V3_PCI") (class "Default")
      (node (ref "C539") (pin "1") (pinfunction "1_1") (pintype "passive"))
      (node (ref "C540") (pin "1") (pinfunction "1_1") (pintype "passive"))
      (node (ref "C544") (pin "1") (pinfunction "1_1") (pintype "passive"))
      (node (ref "C545") (pin "2") (pinfunction "2_2") (pintype "passive"))
      (node (ref "C548") (pin "2") (pinfunction "2_2") (pintype "passive"))
      (node (ref "C560") (pin "1") (pinfunction "1_1") (pintype "passive"))
      (node (ref "C561") (pin "1") (pinfunction "1_1") (pintype "passive"))
      (node (ref "C562") (pin "1") (pinfunction "1_1") (pintype "passive"))
      (node (ref "C563") (pin "1") (pinfunction "1_1") (pintype "passive"))
      (node (ref "C571") (pin "2") (pinfunction "2_2") (pintype "passive"))
      (node (ref "C572") (pin "1") (pinfunction "1_1") (pintype "passive"))
      (node (ref "C573") (pin "1") (pinfunction "1_1") (pintype "passive"))
      (node (ref "C574") (pin "1") (pinfunction "1_1") (pintype "passive"))
      (node (ref "C575") (pin "1") (pinfunction "1_1") (pintype "passive"))
      (node (ref "C594") (pin "1") (pinfunction "1_1") (pintype "passive"))
      (node (ref "C595") (pin "1") (pinfunction "1_1") (pintype "passive"))
      (node (ref "C596") (pin "1") (pinfunction "1_1") (pintype "passive"))
      (node (ref "C597") (pin "1") (pinfunction "1_1") (pintype "passive"))
      (node (ref "C602") (pin "2") (pinfunction "2_2") (pintype "passive"))
      (node (ref "D54") (pin "1") (pinfunction "A_1") (pintype "passive"))
      (node (ref "D59") (pin "1") (pinfunction "VCC_1") (pintype "passive"))
      (node (ref "D60") (pin "3") (pinfunction "K_3") (pintype "passive"))
      (node (ref "D61") (pin "3") (pinfunction "K_3") (pintype "passive"))
      (node (ref "D62") (pin "3") (pinfunction "K_3") (pintype "passive"))
      (node (ref "D63") (pin "3") (pinfunction "K_3") (pintype "passive"))
      (node (ref "D64") (pin "3") (pinfunction "K_3") (pintype "passive"))
      (node (ref "D65") (pin "3") (pinfunction "K_3") (pintype "passive"))
      (node (ref "D66") (pin "3") (pinfunction "K_3") (pintype "passive"))
      (node (ref "D67") (pin "3") (pinfunction "K_3") (pintype "passive"))
      (node (ref "D68") (pin "3") (pinfunction "K_3") (pintype "passive"))
      (node (ref "J19") (pin "A10") (pinfunction "+3V3_A10") (pintype "power_in"))
      (node (ref "J19") (pin "A9") (pinfunction "+3V3_A9") (pintype "power_in"))
      (node (ref "J19") (pin "B8") (pinfunction "+3V3_B8") (pintype "power_in"))
      (node (ref "R337") (pin "1") (pinfunction "1_1") (pintype "passive"))
      (node (ref "R341") (pin "1") (pinfunction "1_1") (pintype "passive"))
      (node (ref "TP151") (pin "1") (pinfunction "A_1") (pintype "passive"))
      (node (ref "U42") (pin "1") (pinfunction "VCC1_1") (pintype "passive"))
      (node (ref "U42") (pin "7") (pinfunction "EN1_7") (pintype "passive"))
      (node (ref "U43") (pin "1") (pinfunction "VIN1_1") (pintype "power_in"))
      (node (ref "U44") (pin "1") (pinfunction "VDD1_1") (pintype "passive"))
      (node (ref "U45") (pin "1") (pinfunction "VIN1_1") (pintype "power_in"))
      (node (ref "U46") (pin "17") (pinfunction "VDDISO_17") (pintype "power_in"))
    )
    (net (code "5") (name "+12V_PCI") (class "Default")
      (node (ref "C556") (pin "1") (pinfunction "1_1") (pintype "passive"))
      (node (ref "C557") (pin "1") (pinfunction "1_1") (pintype "passive"))
      (node (ref "C558") (pin "1") (pinfunction "1_1") (pintype "passive"))
      (node (ref "C559") (pin "1") (pinfunction "1_1") (pintype "passive"))
      (node (ref "D55") (pin "1") (pinfunction "A_1") (pintype "passive"))
      (node (ref "J19") (pin "A2") (pinfunction "+12V_A2") (pintype "power_in"))
      (node (ref "J19") (pin "A3") (pinfunction "+12V_A3") (pintype "power_in"))
      (node (ref "J19") (pin "B1") (pinfunction "+12V_B1") (pintype "power_in"))
      (node (ref "J19") (pin "B2") (pinfunction "+12V_B2") (pintype "power_in"))
      (node (ref "J19") (pin "B3") (pinfunction "+12V_B3") (pintype "power_in"))
      (node (ref "R336") (pin "1") (pinfunction "1_1") (pintype "passive"))
      (node (ref "TP150") (pin "1") (pinfunction "A_1") (pintype "passive"))
    )
    (net (code "6") (name "/HOT_PLUG") (class "Default")
      (node (ref "J19") (pin "A1") (pinfunction "PRSNT1_A1") (pintype "passive"))
      (node (ref "J19") (pin "B17") (pinfunction "PRSNT2_B17") (pintype "passive"))
      (node (ref "TP139") (pin "1") (pinfunction "A_1") (pintype "passive"))
      (node (ref "U44") (pin "6") (pinfunction "A4_6") (pintype "passive"))
    )
    (net (code "7") (name "/HSI0_N") (class "Default")
      (node (ref "R334") (pin "2") (pinfunction "2_2") (pintype "passive"))
      (node (ref "U43") (pin "15") (pinfunction "DIN1-_15") (pintype "input"))
    )
    (net (code "8") (name "/HSI0_P") (class "Default")
      (node (ref "R334") (pin "1") (pinfunction "1_1") (pintype "passive"))
      (node (ref "U43") (pin "16") (pinfunction "DIN1+_16") (pintype "input"))
    )
    (net (code "9") (name "/HSO0_N") (class "Default")
      (node (ref "U43") (pin "13") (pinfunction "DOUT2-_13") (pintype "output"))
    )
    (net (code "10") (name "/HSO0_P") (class "Default")
      (node (ref "U43") (pin "14") (pinfunction "DOUT2+_14") (pintype "output"))
    )
    (net (code "11") (name "/PCI_HSI0_N") (class "Default")
      (node (ref "C538") (pin "1") (pinfunction "1_1") (pintype "passive"))
      (node (ref "D58") (pin "5") (pinfunction "D2-_5") (pintype "passive"))
      (node (ref "D58") (pin "6") (pinfunction "NC_6") (pintype "passive"))
      (node (ref "J19") (pin "A17") (pinfunction "HSI-0_A17") (pintype "input"))
      (node (ref "TP137") (pin "1") (pinfunction "A_1") (pintype "passive"))
    )
    (net (code "12") (name "/PCI_HSI0_P") (class "Default")
      (node (ref "C537") (pin "1") (pinfunction "1_1") (pintype "passive"))
      (node (ref "D58") (pin "4") (pinfunction "D2+_4") (pintype "passive"))
      (node (ref "D58") (pin "7") (pinfunction "NC_7") (pintype "passive"))
      (node (ref "J19") (pin "A16") (pinfunction "HSI+0_A16") (pintype "input"))
      (node (ref "TP136") (pin "1") (pinfunction "A_1") (pintype "passive"))
    )
    (net (code "13") (name "/PCI_HSO0_N") (class "Default")
      (node (ref "D58") (pin "2") (pinfunction "D1-_2") (pintype "passive"))
      (node (ref "D58") (pin "9") (pinfunction "NC_9") (pintype "passive"))
      (node (ref "J19") (pin "B15") (pinfunction "HSO-0_B15") (pintype "output"))
      (node (ref "R335") (pin "2") (pinfunction "2_2") (pintype "passive"))
      (node (ref "TP140") (pin "1") (pinfunction "A_1") (pintype "passive"))
      (node (ref "U43") (pin "8") (pinfunction "DIN2-_8") (pintype "input"))
    )
    (net (code "14") (name "/PCI_HSO0_P") (class "Default")
      (node (ref "D58") (pin "1") (pinfunction "D1+_1") (pintype "passive"))
      (node (ref "D58") (pin "10") (pinfunction "NC_10") (pintype "passive"))
      (node (ref "J19") (pin "B14") (pinfunction "HSO+0_B14") (pintype "output"))
      (node (ref "R335") (pin "1") (pinfunction "1_1") (pintype "passive"))
      (node (ref "TP138") (pin "1") (pinfunction "A_1") (pintype "passive"))
      (node (ref "U43") (pin "7") (pinfunction "DIN2+_7") (pintype "input"))
    )
    (net (code "15") (name "/PCI_PERST") (class "Default")
      (node (ref "D65") (pin "2") (pinfunction "K_2") (pintype "passive"))
      (node (ref "J19") (pin "A11") (pinfunction "PERST_A11") (pintype "output"))
      (node (ref "TP159") (pin "1") (pinfunction "A_1") (pintype "passive"))
      (node (ref "U44") (pin "5") (pinfunction "A3_5") (pintype "passive"))
    )
    (net (code "16") (name "/PCI_REFCLK_N") (class "Default")
      (node (ref "D59") (pin "5") (pinfunction "IO2_5") (pintype "passive"))
      (node (ref "J19") (pin "A14") (pinfunction "REFCLK-_A14") (pintype "output"))
      (node (ref "R342") (pin "2") (pinfunction "2_2") (pintype "passive"))
      (node (ref "TP147") (pin "1") (pinfunction "A_1") (pintype "passive"))
      (node (ref "U45") (pin "8") (pinfunction "DIN2-_8") (pintype "input"))
    )
    (net (code "17") (name "/PCI_REFCLK_P") (class "Default")
      (node (ref "D59") (pin "3") (pinfunction "IO1_3") (pintype "passive"))
      (node (ref "J19") (pin "A13") (pinfunction "REFCLK+_A13") (pintype "output"))
      (node (ref "R342") (pin "1") (pinfunction "1_1") (pintype "passive"))
      (node (ref "TP146") (pin "1") (pinfunction "A_1") (pintype "passive"))
      (node (ref "U45") (pin "7") (pinfunction "DIN2+_7") (pintype "input"))
    )
    (net (code "18") (name "/PCI_SMCLK") (class "Default")
      (node (ref "D67") (pin "2") (pinfunction "K_2") (pintype "passive"))
      (node (ref "J19") (pin "B5") (pinfunction "SMCLK_B5") (pintype "bidirectional"))
      (node (ref "TP161") (pin "1") (pinfunction "A_1") (pintype "passive"))
      (node (ref "U46") (pin "19") (pinfunction "SCL1_19") (pintype "bidirectional"))
    )
    (net (code "19") (name "/PCI_SMDAT") (class "Default")
      (node (ref "D68") (pin "2") (pinfunction "K_2") (pintype "passive"))
      (node (ref "J19") (pin "B6") (pinfunction "SMDAT_B6") (pintype "bidirectional"))
      (node (ref "TP162") (pin "1") (pinfunction "A_1") (pintype "passive"))
      (node (ref "U46") (pin "18") (pinfunction "SDA1_18") (pintype "bidirectional"))
    )
    (net (code "20") (name "/PCI_TCK") (class "Default")
      (node (ref "D60") (pin "2") (pinfunction "K_2") (pintype "passive"))
      (node (ref "J19") (pin "A5") (pinfunction "TCK_A5") (pintype "output"))
      (node (ref "TP153") (pin "1") (pinfunction "A_1") (pintype "passive"))
      (node (ref "U42") (pin "3") (pinfunction "INA_3") (pintype "passive"))
    )
    (net (code "21") (name "/PCI_TDI") (class "Default")
      (node (ref "D61") (pin "2") (pinfunction "K_2") (pintype "passive"))
      (node (ref "J19") (pin "A6") (pinfunction "TDI_A6") (pintype "output"))
      (node (ref "TP154") (pin "1") (pinfunction "A_1") (pintype "passive"))
      (node (ref "U42") (pin "5") (pinfunction "INC_5") (pintype "passive"))
    )
    (net (code "22") (name "/PCI_TDO") (class "Default")
      (node (ref "D62") (pin "2") (pinfunction "K_2") (pintype "passive"))
      (node (ref "J19") (pin "A7") (pinfunction "TDO_A7") (pintype "input"))
      (node (ref "TP155") (pin "1") (pinfunction "A_1") (pintype "passive"))
      (node (ref "U42") (pin "6") (pinfunction "OUTD_6") (pintype "passive"))
    )
    (net (code "23") (name "/PCI_TMS") (class "Default")
      (node (ref "D63") (pin "2") (pinfunction "K_2") (pintype "passive"))
      (node (ref "J19") (pin "A8") (pinfunction "TMS_A8") (pintype "output"))
      (node (ref "TP157") (pin "1") (pinfunction "A_1") (pintype "passive"))
      (node (ref "U42") (pin "4") (pinfunction "INB_4") (pintype "passive"))
    )
    (net (code "24") (name "/PCI_TRST") (class "Default")
      (node (ref "D64") (pin "2") (pinfunction "K_2") (pintype "passive"))
      (node (ref "J19") (pin "B9") (pinfunction "TRST_B9") (pintype "output"))
      (node (ref "TP158") (pin "1") (pinfunction "A_1") (pintype "passive"))
      (node (ref "U44") (pin "4") (pinfunction "A2_4") (pintype "passive"))
    )
    (net (code "25") (name "/PCI_WAKE") (class "Default")
      (node (ref "D66") (pin "2") (pinfunction "K_2") (pintype "passive"))
      (node (ref "J19") (pin "B11") (pinfunction "WAKE_B11") (pintype "output"))
      (node (ref "TP160") (pin "1") (pinfunction "A_1") (pintype "passive"))
      (node (ref "U44") (pin "3") (pinfunction "A1_3") (pintype "passive"))
    )
    (net (code "26") (name "/PERST_PCI") (class "Default")
      (node (ref "TP142") (pin "1") (pinfunction "A_1") (pintype "passive"))
      (node (ref "U44") (pin "12") (pinfunction "B3_12") (pintype "passive"))
    )
    (net (code "27") (name "/PRSNT_PCI") (class "Default")
      (node (ref "TP143") (pin "1") (pinfunction "A_1") (pintype "passive"))
      (node (ref "U44") (pin "11") (pinfunction "B4_11") (pintype "passive"))
    )
    (net (code "28") (name "/REFCLK_N") (class "Default")
      (node (ref "U45") (pin "13") (pinfunction "DOUT2-_13") (pintype "output"))
    )
    (net (code "29") (name "/REFCLK_P") (class "Default")
      (node (ref "U45") (pin "14") (pinfunction "DOUT2+_14") (pintype "output"))
    )
    (net (code "30") (name "/SMCLK_PCI") (class "Default")
      (node (ref "TP144") (pin "1") (pinfunction "A_1") (pintype "passive"))
      (node (ref "U46") (pin "2") (pinfunction "SCL2_2") (pintype "bidirectional"))
    )
    (net (code "31") (name "/SMDAT_PCI") (class "Default")
      (node (ref "TP145") (pin "1") (pinfunction "A_1") (pintype "passive"))
      (node (ref "U46") (pin "3") (pinfunction "SDA2_3") (pintype "bidirectional"))
    )
    (net (code "32") (name "/TCK_PCI") (class "Default")
      (node (ref "U42") (pin "14") (pinfunction "OUTA_14") (pintype "passive"))
    )
    (net (code "33") (name "/TDI_PCI") (class "Default")
      (node (ref "U42") (pin "12") (pinfunction "OUTC_12") (pintype "passive"))
    )
    (net (code "34") (name "/TDO_PCI") (class "Default")
      (node (ref "U42") (pin "11") (pinfunction "IND_11") (pintype "passive"))
    )
    (net (code "35") (name "/TMS_PCI") (class "Default")
      (node (ref "U42") (pin "13") (pinfunction "OUTB_13") (pintype "passive"))
    )
    (net (code "36") (name "/TRST_PCI") (class "Default")
      (node (ref "U44") (pin "14") (pinfunction "B1_14") (pintype "passive"))
    )
    (net (code "37") (name "/WAKE_PCI") (class "Default")
      (node (ref "TP141") (pin "1") (pinfunction "A_1") (pintype "passive"))
      (node (ref "U44") (pin "13") (pinfunction "B2_13") (pintype "passive"))
    )
    (net (code "40") (name "GND") (class "Default")
      (node (ref "C541") (pin "2") (pinfunction "2_2") (pintype "passive"))
      (node (ref "C542") (pin "2") (pinfunction "2_2") (pintype "passive"))
      (node (ref "C543") (pin "2") (pinfunction "2_2") (pintype "passive"))
      (node (ref "C546") (pin "2") (pinfunction "2_2") (pintype "passive"))
      (node (ref "C547") (pin "2") (pinfunction "2_2") (pintype "passive"))
      (node (ref "C564") (pin "2") (pinfunction "2_2") (pintype "passive"))
      (node (ref "C565") (pin "2") (pinfunction "2_2") (pintype "passive"))
      (node (ref "C566") (pin "2") (pinfunction "2_2") (pintype "passive"))
      (node (ref "C567") (pin "2") (pinfunction "2_2") (pintype "passive"))
      (node (ref "C568") (pin "2") (pinfunction "2_2") (pintype "passive"))
      (node (ref "C569") (pin "2") (pinfunction "2_2") (pintype "passive"))
      (node (ref "C570") (pin "2") (pinfunction "2_2") (pintype "passive"))
      (node (ref "C576") (pin "2") (pinfunction "2_2") (pintype "passive"))
      (node (ref "C577") (pin "2") (pinfunction "2_2") (pintype "passive"))
      (node (ref "C578") (pin "2") (pinfunction "2_2") (pintype "passive"))
      (node (ref "C579") (pin "2") (pinfunction "2_2") (pintype "passive"))
      (node (ref "C587") (pin "2") (pinfunction "2_2") (pintype "passive"))
      (node (ref "C588") (pin "2") (pinfunction "2_2") (pintype "passive"))
      (node (ref "C589") (pin "2") (pinfunction "2_2") (pintype "passive"))
      (node (ref "C590") (pin "2") (pinfunction "2_2") (pintype "passive"))
      (node (ref "C591") (pin "2") (pinfunction "2_2") (pintype "passive"))
      (node (ref "C592") (pin "2") (pinfunction "2_2") (pintype "passive"))
      (node (ref "C593") (pin "2") (pinfunction "2_2") (pintype "passive"))
      (node (ref "C598") (pin "2") (pinfunction "2_2") (pintype "passive"))
      (node (ref "C599") (pin "2") (pinfunction "2_2") (pintype "passive"))
      (node (ref "C600") (pin "2") (pinfunction "2_2") (pintype "passive"))
      (node (ref "C601") (pin "2") (pinfunction "2_2") (pintype "passive"))
      (node (ref "R339") (pin "1") (pinfunction "1_1") (pintype "passive"))
      (node (ref "R343") (pin "2") (pinfunction "2_2") (pintype "passive"))
      (node (ref "TP149") (pin "1") (pinfunction "A_1") (pintype "passive"))
      (node (ref "U42") (pin "15") (pinfunction "GND2_15") (pintype "passive"))
      (node (ref "U42") (pin "9") (pinfunction "GND2_9") (pintype "passive"))
      (node (ref "U43") (pin "11") (pinfunction "GND2_11") (pintype "power_in"))
      (node (ref "U43") (pin "17") (pinfunction "GND2_17") (pintype "power_in"))
      (node (ref "U43") (pin "19") (pinfunction "GND2_19") (pintype "power_in"))
      (node (ref "U44") (pin "15") (pinfunction "GND2_15") (pintype "passive"))
      (node (ref "U44") (pin "9") (pinfunction "GND2_9") (pintype "passive"))
      (node (ref "U45") (pin "11") (pinfunction "GND2_11") (pintype "power_in"))
      (node (ref "U45") (pin "17") (pinfunction "GND2_17") (pintype "power_in"))
      (node (ref "U45") (pin "19") (pinfunction "GND2_19") (pintype "power_in"))
      (node (ref "U46") (pin "1") (pinfunction "GNDP_1") (pintype "power_in"))
      (node (ref "U46") (pin "10") (pinfunction "GNDP_10") (pintype "power_in"))
      (node (ref "U46") (pin "5") (pinfunction "GNDP_5") (pintype "power_in"))
      (node (ref "U46") (pin "7") (pinfunction "GNDP_7") (pintype "power_in"))
    )
    (net (code "41") (name "Net-(D56-A)") (class "Default")
      (node (ref "D56") (pin "1") (pinfunction "A_1") (pintype "passive"))
      (node (ref "R336") (pin "2") (pinfunction "2_2") (pintype "passive"))
    )
    (net (code "42") (name "Net-(D57-A)") (class "Default")
      (node (ref "D57") (pin "1") (pinfunction "A_1") (pintype "passive"))
      (node (ref "R337") (pin "2") (pinfunction "2_2") (pintype "passive"))
    )
    (net (code "43") (name "Net-(U43-DOUT1+)") (class "Default")
      (node (ref "C537") (pin "2") (pinfunction "2_2") (pintype "passive"))
      (node (ref "U43") (pin "5") (pinfunction "DOUT1+_5") (pintype "output"))
    )
    (net (code "44") (name "Net-(U43-DOUT1-)") (class "Default")
      (node (ref "C538") (pin "2") (pinfunction "2_2") (pintype "passive"))
      (node (ref "U43") (pin "6") (pinfunction "DOUT1-_6") (pintype "output"))
    )
    (net (code "45") (name "Net-(U45-DIN1+)") (class "Default")
      (node (ref "R338") (pin "1") (pinfunction "1_1") (pintype "passive"))
      (node (ref "U45") (pin "16") (pinfunction "DIN1+_16") (pintype "input"))
    )
    (net (code "46") (name "Net-(U45-DIN1-)") (class "Default")
      (node (ref "R339") (pin "2") (pinfunction "2_2") (pintype "passive"))
      (node (ref "U45") (pin "15") (pinfunction "DIN1-_15") (pintype "input"))
    )
    (net (code "47") (name "Net-(U46-PDIS)") (class "Default")
      (node (ref "R340") (pin "2") (pinfunction "2_2") (pintype "passive"))
      (node (ref "R343") (pin "1") (pinfunction "1_1") (pintype "passive"))
      (node (ref "U46") (pin "8") (pinfunction "PDIS_8") (pintype "input"))
    )
    (net (code "48") (name "Net-(U46-VSEL)") (class "Default")
      (node (ref "R341") (pin "2") (pinfunction "2_2") (pintype "passive"))
      (node (ref "R344") (pin "1") (pinfunction "1_1") (pintype "passive"))
      (node (ref "U46") (pin "13") (pinfunction "VSEL_13") (pintype "passive"))
    )
    (net (code "49") (name "PCI_GND") (class "Default")
      (node (ref "C539") (pin "2") (pinfunction "2_2") (pintype "passive"))
      (node (ref "C540") (pin "2") (pinfunction "2_2") (pintype "passive"))
      (node (ref "C543") (pin "1") (pinfunction "1_1") (pintype "passive"))
      (node (ref "C544") (pin "2") (pinfunction "2_2") (pintype "passive"))
      (node (ref "C545") (pin "1") (pinfunction "1_1") (pintype "passive"))
      (node (ref "C548") (pin "1") (pinfunction "1_1") (pintype "passive"))
      (node (ref "C549") (pin "2") (pinfunction "2_2") (pintype "passive"))
      (node (ref "C550") (pin "2") (pinfunction "2_2") (pintype "passive"))
      (node (ref "C551") (pin "2") (pinfunction "2_2") (pintype "passive"))
      (node (ref "C552") (pin "2") (pinfunction "2_2") (pintype "passive"))
      (node (ref "C553") (pin "2") (pinfunction "2_2") (pintype "passive"))
      (node (ref "C554") (pin "2") (pinfunction "2_2") (pintype "passive"))
      (node (ref "C555") (pin "2") (pinfunction "2_2") (pintype "passive"))
      (node (ref "C556") (pin "2") (pinfunction "2_2") (pintype "passive"))
      (node (ref "C557") (pin "2") (pinfunction "2_2") (pintype "passive"))
      (node (ref "C558") (pin "2") (pinfunction "2_2") (pintype "passive"))
      (node (ref "C559") (pin "2") (pinfunction "2_2") (pintype "passive"))
      (node (ref "C560") (pin "2") (pinfunction "2_2") (pintype "passive"))
      (node (ref "C561") (pin "2") (pinfunction "2_2") (pintype "passive"))
      (node (ref "C562") (pin "2") (pinfunction "2_2") (pintype "passive"))
      (node (ref "C563") (pin "2") (pinfunction "2_2") (pintype "passive"))
      (node (ref "C571") (pin "1") (pinfunction "1_1") (pintype "passive"))
      (node (ref "C572") (pin "2") (pinfunction "2_2") (pintype "passive"))
      (node (ref "C573") (pin "2") (pinfunction "2_2") (pintype "passive"))
      (node (ref "C574") (pin "2") (pinfunction "2_2") (pintype "passive"))
      (node (ref "C575") (pin "2") (pinfunction "2_2") (pintype "passive"))
      (node (ref "C580") (pin "2") (pinfunction "2_2") (pintype "passive"))
      (node (ref "C581") (pin "2") (pinfunction "2_2") (pintype "passive"))
      (node (ref "C582") (pin "2") (pinfunction "2_2") (pintype "passive"))
      (node (ref "C583") (pin "2") (pinfunction "2_2") (pintype "passive"))
      (node (ref "C584") (pin "2") (pinfunction "2_2") (pintype "passive"))
      (node (ref "C585") (pin "2") (pinfunction "2_2") (pintype "passive"))
      (node (ref "C586") (pin "2") (pinfunction "2_2") (pintype "passive"))
      (node (ref "C594") (pin "2") (pinfunction "2_2") (pintype "passive"))
      (node (ref "C595") (pin "2") (pinfunction "2_2") (pintype "passive"))
      (node (ref "C596") (pin "2") (pinfunction "2_2") (pintype "passive"))
      (node (ref "C597") (pin "2") (pinfunction "2_2") (pintype "passive"))
      (node (ref "C602") (pin "1") (pinfunction "1_1") (pintype "passive"))
      (node (ref "D54") (pin "2") (pinfunction "C_2") (pintype "passive"))
      (node (ref "D55") (pin "2") (pinfunction "C_2") (pintype "passive"))
      (node (ref "D56") (pin "2") (pinfunction "K_2") (pintype "passive"))
      (node (ref "D57") (pin "2") (pinfunction "K_2") (pintype "passive"))
      (node (ref "D58") (pin "3") (pinfunction "GND_3") (pintype "passive"))
      (node (ref "D58") (pin "8") (pinfunction "GND_8") (pintype "passive"))
      (node (ref "D59") (pin "4") (pinfunction "GND_4") (pintype "passive"))
      (node (ref "D60") (pin "1") (pinfunction "A_1") (pintype "passive"))
      (node (ref "D61") (pin "1") (pinfunction "A_1") (pintype "passive"))
      (node (ref "D62") (pin "1") (pinfunction "A_1") (pintype "passive"))
      (node (ref "D63") (pin "1") (pinfunction "A_1") (pintype "passive"))
      (node (ref "D64") (pin "1") (pinfunction "A_1") (pintype "passive"))
      (node (ref "D65") (pin "1") (pinfunction "A_1") (pintype "passive"))
      (node (ref "D66") (pin "1") (pinfunction "A_1") (pintype "passive"))
      (node (ref "D67") (pin "1") (pinfunction "A_1") (pintype "passive"))
      (node (ref "D68") (pin "1") (pinfunction "A_1") (pintype "passive"))
      (node (ref "J19") (pin "A12") (pinfunction "GND_A12") (pintype "input"))
      (node (ref "J19") (pin "A15") (pinfunction "GND_A15") (pintype "power_in"))
      (node (ref "J19") (pin "A18") (pinfunction "GND_A18") (pintype "power_in"))
      (node (ref "J19") (pin "A4") (pinfunction "GND_A4") (pintype "power_in"))
      (node (ref "J19") (pin "B13") (pinfunction "GND_B13") (pintype "power_in"))
      (node (ref "J19") (pin "B16") (pinfunction "GND_B16") (pintype "power_in"))
      (node (ref "J19") (pin "B18") (pinfunction "GND_B18") (pintype "power_in"))
      (node (ref "J19") (pin "B4") (pinfunction "GND_B4") (pintype "power_in"))
      (node (ref "J19") (pin "B7") (pinfunction "GND_B7") (pintype "power_in"))
      (node (ref "R344") (pin "2") (pinfunction "2_2") (pintype "passive"))
      (node (ref "TP148") (pin "1") (pinfunction "A_1") (pintype "passive"))
      (node (ref "U42") (pin "2") (pinfunction "GND1_2") (pintype "passive"))
      (node (ref "U42") (pin "8") (pinfunction "GND1_8") (pintype "passive"))
      (node (ref "U43") (pin "10") (pinfunction "GND1_10") (pintype "power_in"))
      (node (ref "U43") (pin "2") (pinfunction "GND1_2") (pintype "power_in"))
      (node (ref "U43") (pin "4") (pinfunction "GND1_4") (pintype "power_in"))
      (node (ref "U44") (pin "2") (pinfunction "GND1_2") (pintype "passive"))
      (node (ref "U44") (pin "8") (pinfunction "GND1_8") (pintype "passive"))
      (node (ref "U45") (pin "10") (pinfunction "GND1_10") (pintype "power_in"))
      (node (ref "U45") (pin "2") (pinfunction "GND1_2") (pintype "power_in"))
      (node (ref "U45") (pin "4") (pinfunction "GND1_4") (pintype "power_in"))
      (node (ref "U46") (pin "11") (pinfunction "GNDISO_11") (pintype "power_in"))
      (node (ref "U46") (pin "14") (pinfunction "GNDISO_14") (pintype "power_in"))
      (node (ref "U46") (pin "16") (pinfunction "GNDISO_16") (pintype "power_in"))
      (node (ref "U46") (pin "20") (pinfunction "GNDISO_20") (pintype "power_in"))
    )
    (net (code "50") (name "VDD1_PCI_1") (class "Default")
      (node (ref "C549") (pin "1") (pinfunction "1_1") (pintype "passive"))
      (node (ref "C550") (pin "1") (pinfunction "1_1") (pintype "passive"))
      (node (ref "C551") (pin "1") (pinfunction "1_1") (pintype "passive"))
      (node (ref "C552") (pin "1") (pinfunction "1_1") (pintype "passive"))
      (node (ref "C553") (pin "1") (pinfunction "1_1") (pintype "passive"))
      (node (ref "C554") (pin "1") (pinfunction "1_1") (pintype "passive"))
      (node (ref "C555") (pin "1") (pinfunction "1_1") (pintype "passive"))
      (node (ref "TP152") (pin "1") (pinfunction "A_1") (pintype "passive"))
      (node (ref "U43") (pin "3") (pinfunction "VDD1_3") (pintype "power_in"))
      (node (ref "U43") (pin "9") (pinfunction "VDD1_9") (pintype "power_in"))
    )
    (net (code "51") (name "VDD1_PCI_2") (class "Default")
      (node (ref "C580") (pin "1") (pinfunction "1_1") (pintype "passive"))
      (node (ref "C581") (pin "1") (pinfunction "1_1") (pintype "passive"))
      (node (ref "C582") (pin "1") (pinfunction "1_1") (pintype "passive"))
      (node (ref "C583") (pin "1") (pinfunction "1_1") (pintype "passive"))
      (node (ref "C584") (pin "1") (pinfunction "1_1") (pintype "passive"))
      (node (ref "C585") (pin "1") (pinfunction "1_1") (pintype "passive"))
      (node (ref "C586") (pin "1") (pinfunction "1_1") (pintype "passive"))
      (node (ref "U45") (pin "3") (pinfunction "VDD1_3") (pintype "power_in"))
      (node (ref "U45") (pin "9") (pinfunction "VDD1_9") (pintype "power_in"))
    )
    (net (code "52") (name "VDD2_PCI_1") (class "Default")
      (node (ref "C564") (pin "1") (pinfunction "1_1") (pintype "passive"))
      (node (ref "C565") (pin "1") (pinfunction "1_1") (pintype "passive"))
      (node (ref "C566") (pin "1") (pinfunction "1_1") (pintype "passive"))
      (node (ref "C567") (pin "1") (pinfunction "1_1") (pintype "passive"))
      (node (ref "C568") (pin "1") (pinfunction "1_1") (pintype "passive"))
      (node (ref "C569") (pin "1") (pinfunction "1_1") (pintype "passive"))
      (node (ref "C570") (pin "1") (pinfunction "1_1") (pintype "passive"))
      (node (ref "TP156") (pin "1") (pinfunction "A_1") (pintype "passive"))
      (node (ref "U43") (pin "12") (pinfunction "VDD2_12") (pintype "power_in"))
      (node (ref "U43") (pin "18") (pinfunction "VDD2_18") (pintype "power_in"))
    )
    (net (code "53") (name "VDD2_PCI_2") (class "Default")
      (node (ref "C587") (pin "1") (pinfunction "1_1") (pintype "passive"))
      (node (ref "C588") (pin "1") (pinfunction "1_1") (pintype "passive"))
      (node (ref "C589") (pin "1") (pinfunction "1_1") (pintype "passive"))
      (node (ref "C590") (pin "1") (pinfunction "1_1") (pintype "passive"))
      (node (ref "C591") (pin "1") (pinfunction "1_1") (pintype "passive"))
      (node (ref "C592") (pin "1") (pinfunction "1_1") (pintype "passive"))
      (node (ref "C593") (pin "1") (pinfunction "1_1") (pintype "passive"))
      (node (ref "R338") (pin "2") (pinfunction "2_2") (pintype "passive"))
      (node (ref "U45") (pin "12") (pinfunction "VDD2_12") (pintype "power_in"))
      (node (ref "U45") (pin "18") (pinfunction "VDD2_18") (pintype "power_in"))
    )
    (net (code "54") (name "unconnected-(D59-NC-Pad2)") (class "Default")
      (node (ref "D59") (pin "2") (pinfunction "NC_2") (pintype "passive"))
    )
    (net (code "55") (name "unconnected-(J19-+3V3_AUX-PadB10)") (class "Default")
      (node (ref "J19") (pin "B10") (pinfunction "+3V3_AUX_B10") (pintype "power_in+no_connect"))
    )
    (net (code "56") (name "unconnected-(J19-RSVD-PadB12)") (class "Default")
      (node (ref "J19") (pin "B12") (pinfunction "RSVD_B12") (pintype "passive+no_connect"))
    )
    (net (code "57") (name "unconnected-(U44-NC-Pad7)") (class "Default")
      (node (ref "U44") (pin "7") (pinfunction "NC_7") (pintype "passive+no_connect"))
    )
    (net (code "58") (name "unconnected-(U45-DOUT1+-Pad5)") (class "Default")
      (node (ref "U45") (pin "5") (pinfunction "DOUT1+_5") (pintype "output+no_connect"))
    )
    (net (code "59") (name "unconnected-(U45-DOUT1--Pad6)") (class "Default")
      (node (ref "U45") (pin "6") (pinfunction "DOUT1-_6") (pintype "output+no_connect"))
    )
    (net (code "60") (name "unconnected-(U46-NC-Pad6)") (class "Default")
      (node (ref "U46") (pin "6") (pinfunction "NC_6") (pintype "passive+no_connect"))
    )
    (net (code "61") (name "unconnected-(U46-NC-Pad15)") (class "Default")
      (node (ref "U46") (pin "15") (pinfunction "NC_15") (pintype "passive+no_connect"))
    )
    (net (code "62") (name "unconnected-(U46-VISO-Pad12)") (class "Default")
      (node (ref "U46") (pin "12") (pinfunction "VISO_12") (pintype "power_in+no_connect"))
    )
  )
)
